# TK510_Signalbakplan_-_Kopi.net
KiCad netlist of a schematic drawn in Altium Designer
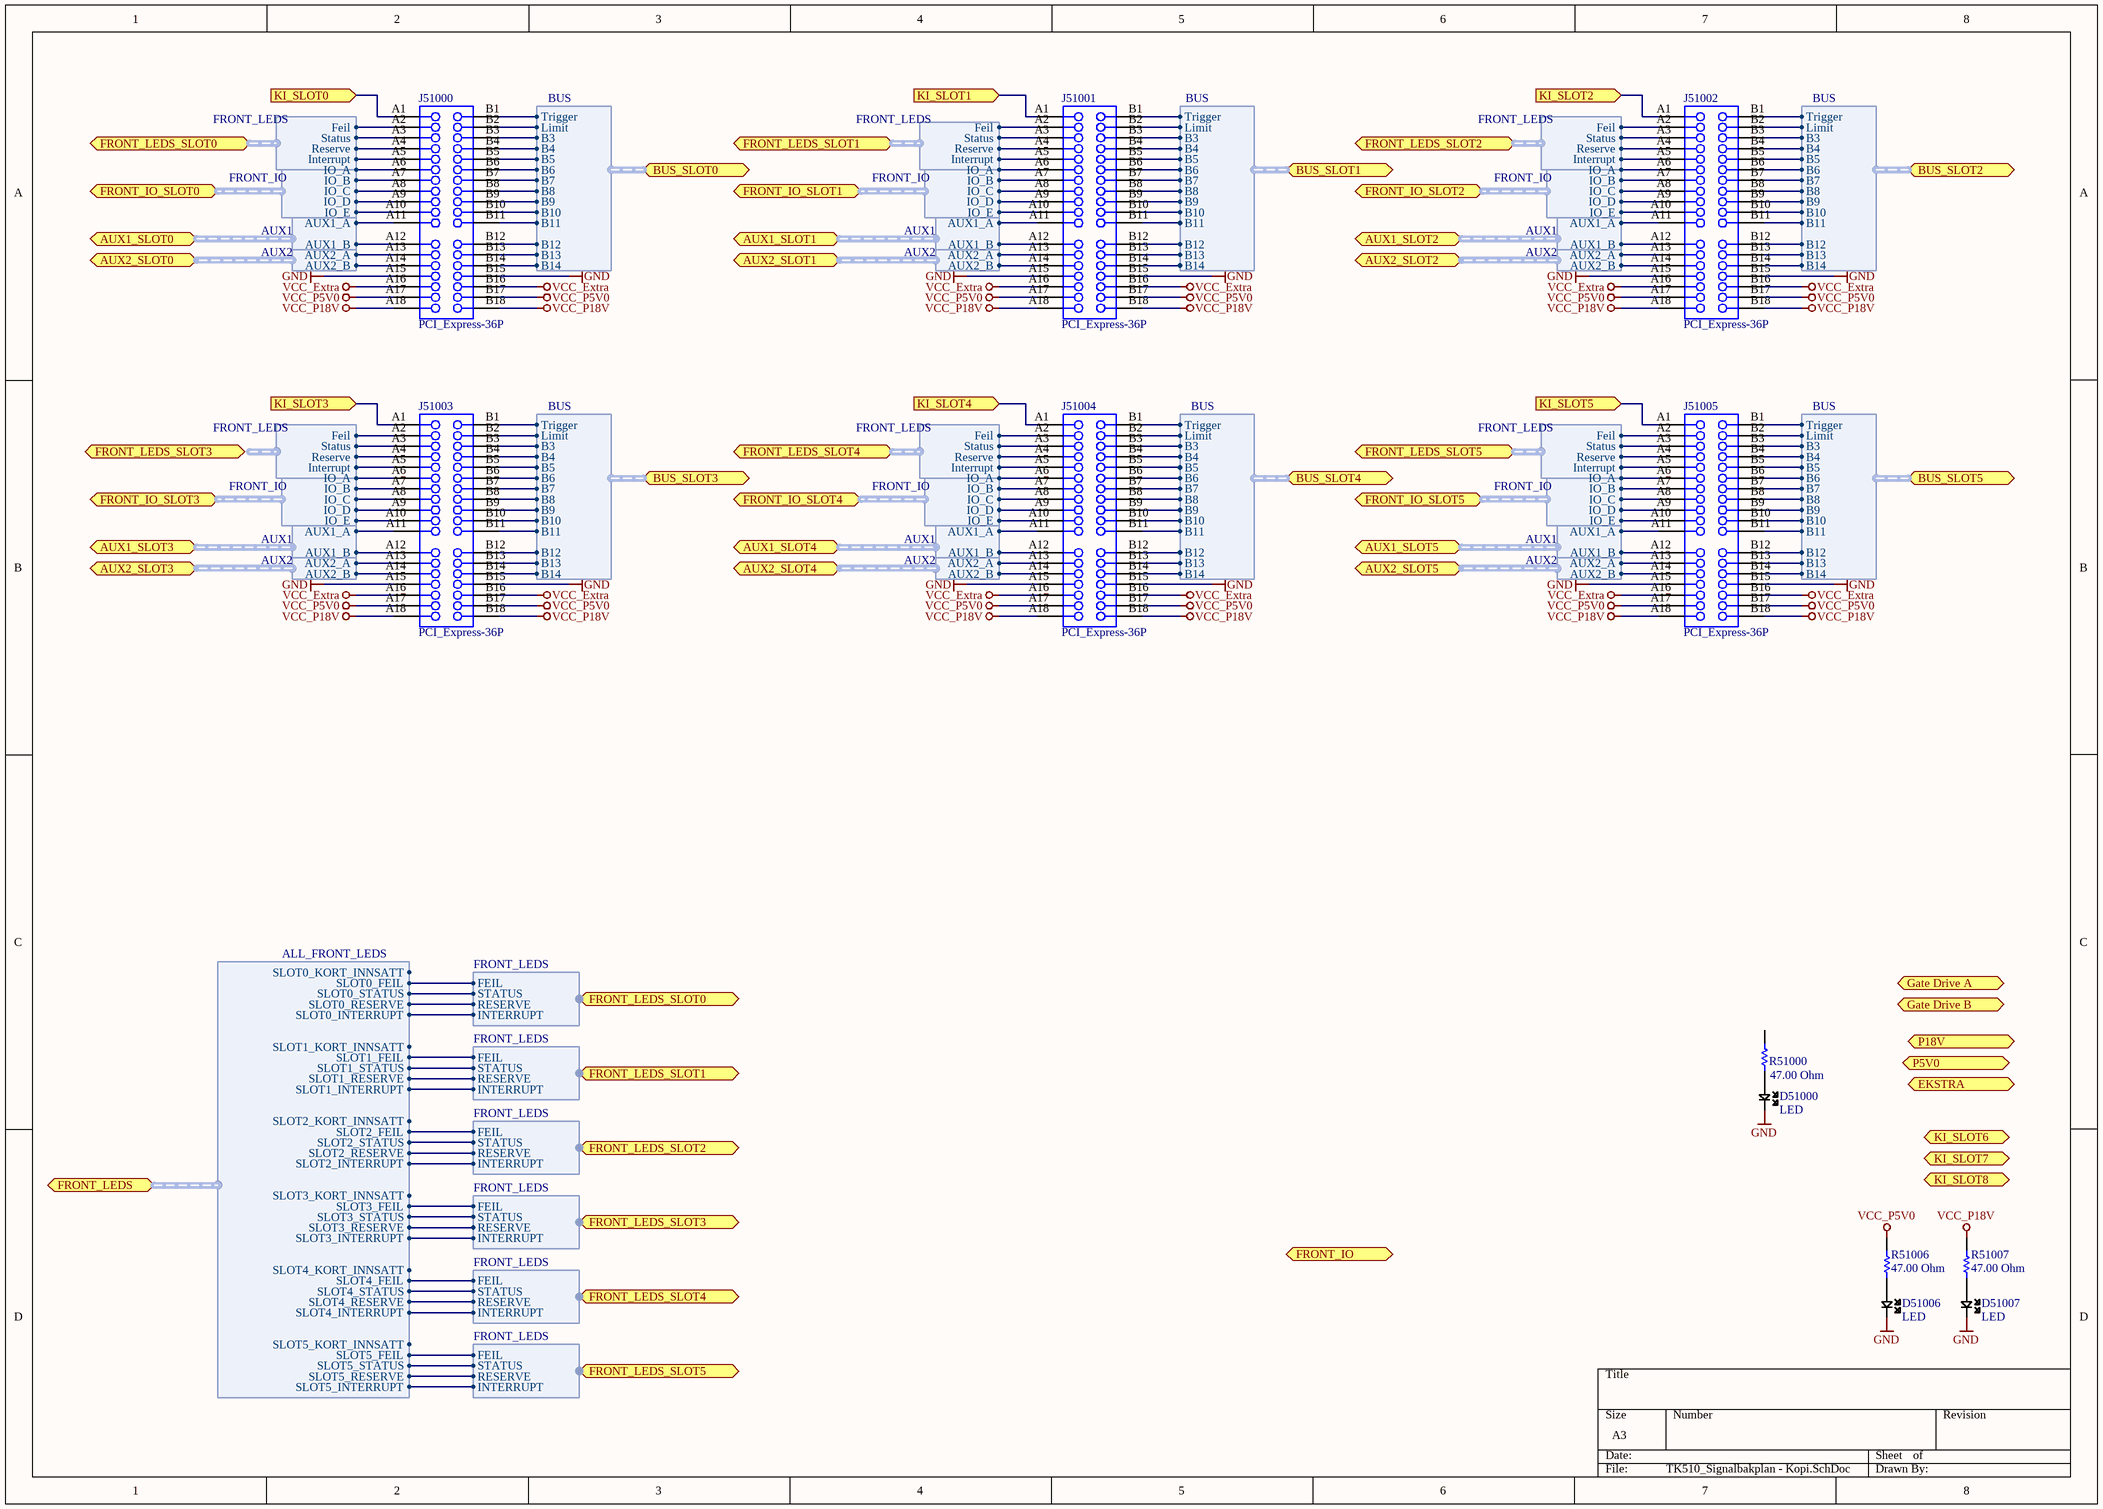
[diagram p0: TK510_Signalbakplan - Kopi.SchDoc]

(export (version "E")
  (design (tool "Eeschema 10.0.6"))
  (components
    (comp (ref "D51000")
      (value "LED")
      (footprint "I_LEDC0603(1608)_N")
      (libsource (lib "OVLib") (part "LED"))
    )
    (comp (ref "D51006")
      (value "LED")
      (footprint "I_LEDC0603(1608)_N")
      (libsource (lib "OVLib") (part "LED"))
    )
    (comp (ref "D51007")
      (value "LED")
      (footprint "I_LEDC0603(1608)_N")
      (libsource (lib "OVLib") (part "LED"))
    )
    (comp (ref "J51000")
      (value "PCI_Express-36P")
      (footprint "PCI_Express-36P")
      (description "Board-to-Board Connector, PTH, Vertical, Pitch 1.00mm, 36-Position")
      (libsource (lib "OVLib") (part "PCI_Express-36P"))
    )
    (comp (ref "J51001")
      (value "PCI_Express-36P")
      (footprint "PCI_Express-36P")
      (description "Board-to-Board Connector, PTH, Vertical, Pitch 1.00mm, 36-Position")
      (libsource (lib "OVLib") (part "PCI_Express-36P"))
    )
    (comp (ref "J51002")
      (value "PCI_Express-36P")
      (footprint "PCI_Express-36P")
      (description "Board-to-Board Connector, PTH, Vertical, Pitch 1.00mm, 36-Position")
      (libsource (lib "OVLib") (part "PCI_Express-36P"))
    )
    (comp (ref "J51003")
      (value "PCI_Express-36P")
      (footprint "PCI_Express-36P")
      (description "Board-to-Board Connector, PTH, Vertical, Pitch 1.00mm, 36-Position")
      (libsource (lib "OVLib") (part "PCI_Express-36P"))
    )
    (comp (ref "J51004")
      (value "PCI_Express-36P")
      (footprint "PCI_Express-36P")
      (description "Board-to-Board Connector, PTH, Vertical, Pitch 1.00mm, 36-Position")
      (libsource (lib "OVLib") (part "PCI_Express-36P"))
    )
    (comp (ref "J51005")
      (value "PCI_Express-36P")
      (footprint "PCI_Express-36P")
      (description "Board-to-Board Connector, PTH, Vertical, Pitch 1.00mm, 36-Position")
      (libsource (lib "OVLib") (part "PCI_Express-36P"))
    )
    (comp (ref "R51000")
      (value "47.00 Ohm")
      (footprint "RESC0603(1608)_M")
      (description "47R 0.1W 5% 0603 (1608 Metric)  SMD")
      (fields (field (name "TOLERANCE") "5 %") (field (name "POWER") "0.1 W"))
      (libsource (lib "Altium Content Vault") (part "CMP-1012-00042-1"))
    )
    (comp (ref "R51006")
      (value "47.00 Ohm")
      (footprint "RESC0603(1608)_M")
      (description "47R 0.1W 5% 0603 (1608 Metric)  SMD")
      (fields (field (name "TOLERANCE") "5 %") (field (name "POWER") "0.1 W"))
      (libsource (lib "Altium Content Vault") (part "CMP-1012-00042-1"))
    )
    (comp (ref "R51007")
      (value "47.00 Ohm")
      (footprint "RESC0603(1608)_M")
      (description "47R 0.1W 5% 0603 (1608 Metric)  SMD")
      (fields (field (name "TOLERANCE") "5 %") (field (name "POWER") "0.1 W"))
      (libsource (lib "Altium Content Vault") (part "CMP-1012-00042-1"))
    )
  )
  (nets
    (net (code "20") (name "/KI_SLOT0") (class "Default")
      (node (ref "J51000") (pin "A1") (pinfunction "A1_A1") (pintype "passive"))
    )
    (net (code "21") (name "/KI_SLOT1") (class "Default")
      (node (ref "J51001") (pin "A1") (pinfunction "A1_A1") (pintype "passive"))
    )
    (net (code "22") (name "/KI_SLOT2") (class "Default")
      (node (ref "J51002") (pin "A1") (pinfunction "A1_A1") (pintype "passive"))
    )
    (net (code "23") (name "/KI_SLOT3") (class "Default")
      (node (ref "J51003") (pin "A1") (pinfunction "A1_A1") (pintype "passive"))
    )
    (net (code "24") (name "/KI_SLOT4") (class "Default")
      (node (ref "J51004") (pin "A1") (pinfunction "A1_A1") (pintype "passive"))
    )
    (net (code "25") (name "/KI_SLOT5") (class "Default")
      (node (ref "J51005") (pin "A1") (pinfunction "A1_A1") (pintype "passive"))
    )
    (net (code "35") (name "GND") (class "Default")
      (node (ref "D51000") (pin "2") (pinfunction "2_2") (pintype "passive"))
      (node (ref "D51006") (pin "2") (pinfunction "2_2") (pintype "passive"))
      (node (ref "D51007") (pin "2") (pinfunction "2_2") (pintype "passive"))
      (node (ref "J51000") (pin "A15") (pinfunction "A15_A15") (pintype "passive"))
      (node (ref "J51000") (pin "B15") (pinfunction "B15_B15") (pintype "passive"))
      (node (ref "J51001") (pin "A15") (pinfunction "A15_A15") (pintype "passive"))
      (node (ref "J51001") (pin "B15") (pinfunction "B15_B15") (pintype "passive"))
      (node (ref "J51002") (pin "A15") (pinfunction "A15_A15") (pintype "passive"))
      (node (ref "J51002") (pin "B15") (pinfunction "B15_B15") (pintype "passive"))
      (node (ref "J51003") (pin "A15") (pinfunction "A15_A15") (pintype "passive"))
      (node (ref "J51003") (pin "B15") (pinfunction "B15_B15") (pintype "passive"))
      (node (ref "J51004") (pin "A15") (pinfunction "A15_A15") (pintype "passive"))
      (node (ref "J51004") (pin "B15") (pinfunction "B15_B15") (pintype "passive"))
      (node (ref "J51005") (pin "A15") (pinfunction "A15_A15") (pintype "passive"))
      (node (ref "J51005") (pin "B15") (pinfunction "B15_B15") (pintype "passive"))
    )
    (net (code "36") (name "Net-(D51000-Pad1)") (class "Default")
      (node (ref "D51000") (pin "1") (pinfunction "1_1") (pintype "passive"))
      (node (ref "R51000") (pin "1") (pinfunction "1_1") (pintype "passive"))
    )
    (net (code "37") (name "Net-(D51006-Pad1)") (class "Default")
      (node (ref "D51006") (pin "1") (pinfunction "1_1") (pintype "passive"))
      (node (ref "R51006") (pin "2") (pinfunction "2_2") (pintype "passive"))
    )
    (net (code "38") (name "Net-(D51007-Pad1)") (class "Default")
      (node (ref "D51007") (pin "1") (pinfunction "1_1") (pintype "passive"))
      (node (ref "R51007") (pin "2") (pinfunction "2_2") (pintype "passive"))
    )
    (net (code "39") (name "VCC_Extra") (class "Default")
      (node (ref "J51000") (pin "A16") (pinfunction "A16_A16") (pintype "passive"))
      (node (ref "J51000") (pin "B16") (pinfunction "B16_B16") (pintype "passive"))
      (node (ref "J51001") (pin "A16") (pinfunction "A16_A16") (pintype "passive"))
      (node (ref "J51001") (pin "B16") (pinfunction "B16_B16") (pintype "passive"))
      (node (ref "J51002") (pin "A16") (pinfunction "A16_A16") (pintype "passive"))
      (node (ref "J51002") (pin "B16") (pinfunction "B16_B16") (pintype "passive"))
      (node (ref "J51003") (pin "A16") (pinfunction "A16_A16") (pintype "passive"))
      (node (ref "J51003") (pin "B16") (pinfunction "B16_B16") (pintype "passive"))
      (node (ref "J51004") (pin "A16") (pinfunction "A16_A16") (pintype "passive"))
      (node (ref "J51004") (pin "B16") (pinfunction "B16_B16") (pintype "passive"))
      (node (ref "J51005") (pin "A16") (pinfunction "A16_A16") (pintype "passive"))
      (node (ref "J51005") (pin "B16") (pinfunction "B16_B16") (pintype "passive"))
    )
    (net (code "40") (name "VCC_P5V0") (class "Default")
      (node (ref "J51000") (pin "A17") (pinfunction "A17_A17") (pintype "passive"))
      (node (ref "J51000") (pin "B17") (pinfunction "B17_B17") (pintype "passive"))
      (node (ref "J51001") (pin "A17") (pinfunction "A17_A17") (pintype "passive"))
      (node (ref "J51001") (pin "B17") (pinfunction "B17_B17") (pintype "passive"))
      (node (ref "J51002") (pin "A17") (pinfunction "A17_A17") (pintype "passive"))
      (node (ref "J51002") (pin "B17") (pinfunction "B17_B17") (pintype "passive"))
      (node (ref "J51003") (pin "A17") (pinfunction "A17_A17") (pintype "passive"))
      (node (ref "J51003") (pin "B17") (pinfunction "B17_B17") (pintype "passive"))
      (node (ref "J51004") (pin "A17") (pinfunction "A17_A17") (pintype "passive"))
      (node (ref "J51004") (pin "B17") (pinfunction "B17_B17") (pintype "passive"))
      (node (ref "J51005") (pin "A17") (pinfunction "A17_A17") (pintype "passive"))
      (node (ref "J51005") (pin "B17") (pinfunction "B17_B17") (pintype "passive"))
      (node (ref "R51006") (pin "1") (pinfunction "1_1") (pintype "passive"))
    )
    (net (code "41") (name "VCC_P18V") (class "Default")
      (node (ref "J51000") (pin "A18") (pinfunction "A18_A18") (pintype "passive"))
      (node (ref "J51000") (pin "B18") (pinfunction "B18_B18") (pintype "passive"))
      (node (ref "J51001") (pin "A18") (pinfunction "A18_A18") (pintype "passive"))
      (node (ref "J51001") (pin "B18") (pinfunction "B18_B18") (pintype "passive"))
      (node (ref "J51002") (pin "A18") (pinfunction "A18_A18") (pintype "passive"))
      (node (ref "J51002") (pin "B18") (pinfunction "B18_B18") (pintype "passive"))
      (node (ref "J51003") (pin "A18") (pinfunction "A18_A18") (pintype "passive"))
      (node (ref "J51003") (pin "B18") (pinfunction "B18_B18") (pintype "passive"))
      (node (ref "J51004") (pin "A18") (pinfunction "A18_A18") (pintype "passive"))
      (node (ref "J51004") (pin "B18") (pinfunction "B18_B18") (pintype "passive"))
      (node (ref "J51005") (pin "A18") (pinfunction "A18_A18") (pintype "passive"))
      (node (ref "J51005") (pin "B18") (pinfunction "B18_B18") (pintype "passive"))
      (node (ref "R51007") (pin "1") (pinfunction "1_1") (pintype "passive"))
    )
    (net (code "42") (name "unconnected-(J51000-PadA2)") (class "Default")
      (node (ref "J51000") (pin "A2") (pinfunction "A2_A2") (pintype "passive"))
    )
    (net (code "43") (name "unconnected-(J51000-PadA3)") (class "Default")
      (node (ref "J51000") (pin "A3") (pinfunction "A3_A3") (pintype "passive"))
    )
    (net (code "44") (name "unconnected-(J51000-PadA4)") (class "Default")
      (node (ref "J51000") (pin "A4") (pinfunction "A4_A4") (pintype "passive"))
    )
    (net (code "45") (name "unconnected-(J51000-PadA5)") (class "Default")
      (node (ref "J51000") (pin "A5") (pinfunction "A5_A5") (pintype "passive"))
    )
    (net (code "46") (name "unconnected-(J51000-PadA6)") (class "Default")
      (node (ref "J51000") (pin "A6") (pinfunction "A6_A6") (pintype "passive"))
    )
    (net (code "47") (name "unconnected-(J51000-PadA7)") (class "Default")
      (node (ref "J51000") (pin "A7") (pinfunction "A7_A7") (pintype "passive"))
    )
    (net (code "48") (name "unconnected-(J51000-PadA8)") (class "Default")
      (node (ref "J51000") (pin "A8") (pinfunction "A8_A8") (pintype "passive"))
    )
    (net (code "49") (name "unconnected-(J51000-PadA9)") (class "Default")
      (node (ref "J51000") (pin "A9") (pinfunction "A9_A9") (pintype "passive"))
    )
    (net (code "50") (name "unconnected-(J51000-PadA10)") (class "Default")
      (node (ref "J51000") (pin "A10") (pinfunction "A10_A10") (pintype "passive"))
    )
    (net (code "51") (name "unconnected-(J51000-PadA11)") (class "Default")
      (node (ref "J51000") (pin "A11") (pinfunction "A11_A11") (pintype "passive"))
    )
    (net (code "52") (name "unconnected-(J51000-PadA12)") (class "Default")
      (node (ref "J51000") (pin "A12") (pinfunction "A12_A12") (pintype "passive"))
    )
    (net (code "53") (name "unconnected-(J51000-PadA13)") (class "Default")
      (node (ref "J51000") (pin "A13") (pinfunction "A13_A13") (pintype "passive"))
    )
    (net (code "54") (name "unconnected-(J51000-PadA14)") (class "Default")
      (node (ref "J51000") (pin "A14") (pinfunction "A14_A14") (pintype "passive"))
    )
    (net (code "55") (name "unconnected-(J51000-PadB1)") (class "Default")
      (node (ref "J51000") (pin "B1") (pinfunction "B1_B1") (pintype "passive"))
    )
    (net (code "56") (name "unconnected-(J51000-PadB2)") (class "Default")
      (node (ref "J51000") (pin "B2") (pinfunction "B2_B2") (pintype "passive"))
    )
    (net (code "57") (name "unconnected-(J51000-PadB3)") (class "Default")
      (node (ref "J51000") (pin "B3") (pinfunction "B3_B3") (pintype "passive"))
    )
    (net (code "58") (name "unconnected-(J51000-PadB4)") (class "Default")
      (node (ref "J51000") (pin "B4") (pinfunction "B4_B4") (pintype "passive"))
    )
    (net (code "59") (name "unconnected-(J51000-PadB5)") (class "Default")
      (node (ref "J51000") (pin "B5") (pinfunction "B5_B5") (pintype "passive"))
    )
    (net (code "60") (name "unconnected-(J51000-PadB6)") (class "Default")
      (node (ref "J51000") (pin "B6") (pinfunction "B6_B6") (pintype "passive"))
    )
    (net (code "61") (name "unconnected-(J51000-PadB7)") (class "Default")
      (node (ref "J51000") (pin "B7") (pinfunction "B7_B7") (pintype "passive"))
    )
    (net (code "62") (name "unconnected-(J51000-PadB8)") (class "Default")
      (node (ref "J51000") (pin "B8") (pinfunction "B8_B8") (pintype "passive"))
    )
    (net (code "63") (name "unconnected-(J51000-PadB9)") (class "Default")
      (node (ref "J51000") (pin "B9") (pinfunction "B9_B9") (pintype "passive"))
    )
    (net (code "64") (name "unconnected-(J51000-PadB10)") (class "Default")
      (node (ref "J51000") (pin "B10") (pinfunction "B10_B10") (pintype "passive"))
    )
    (net (code "65") (name "unconnected-(J51000-PadB11)") (class "Default")
      (node (ref "J51000") (pin "B11") (pinfunction "B11_B11") (pintype "passive"))
    )
    (net (code "66") (name "unconnected-(J51000-PadB12)") (class "Default")
      (node (ref "J51000") (pin "B12") (pinfunction "B12_B12") (pintype "passive"))
    )
    (net (code "67") (name "unconnected-(J51000-PadB13)") (class "Default")
      (node (ref "J51000") (pin "B13") (pinfunction "B13_B13") (pintype "passive"))
    )
    (net (code "68") (name "unconnected-(J51000-PadB14)") (class "Default")
      (node (ref "J51000") (pin "B14") (pinfunction "B14_B14") (pintype "passive"))
    )
    (net (code "69") (name "unconnected-(J51001-PadA2)") (class "Default")
      (node (ref "J51001") (pin "A2") (pinfunction "A2_A2") (pintype "passive"))
    )
    (net (code "70") (name "unconnected-(J51001-PadA3)") (class "Default")
      (node (ref "J51001") (pin "A3") (pinfunction "A3_A3") (pintype "passive"))
    )
    (net (code "71") (name "unconnected-(J51001-PadA4)") (class "Default")
      (node (ref "J51001") (pin "A4") (pinfunction "A4_A4") (pintype "passive"))
    )
    (net (code "72") (name "unconnected-(J51001-PadA5)") (class "Default")
      (node (ref "J51001") (pin "A5") (pinfunction "A5_A5") (pintype "passive"))
    )
    (net (code "73") (name "unconnected-(J51001-PadA6)") (class "Default")
      (node (ref "J51001") (pin "A6") (pinfunction "A6_A6") (pintype "passive"))
    )
    (net (code "74") (name "unconnected-(J51001-PadA7)") (class "Default")
      (node (ref "J51001") (pin "A7") (pinfunction "A7_A7") (pintype "passive"))
    )
    (net (code "75") (name "unconnected-(J51001-PadA8)") (class "Default")
      (node (ref "J51001") (pin "A8") (pinfunction "A8_A8") (pintype "passive"))
    )
    (net (code "76") (name "unconnected-(J51001-PadA9)") (class "Default")
      (node (ref "J51001") (pin "A9") (pinfunction "A9_A9") (pintype "passive"))
    )
    (net (code "77") (name "unconnected-(J51001-PadA10)") (class "Default")
      (node (ref "J51001") (pin "A10") (pinfunction "A10_A10") (pintype "passive"))
    )
    (net (code "78") (name "unconnected-(J51001-PadA11)") (class "Default")
      (node (ref "J51001") (pin "A11") (pinfunction "A11_A11") (pintype "passive"))
    )
    (net (code "79") (name "unconnected-(J51001-PadA12)") (class "Default")
      (node (ref "J51001") (pin "A12") (pinfunction "A12_A12") (pintype "passive"))
    )
    (net (code "80") (name "unconnected-(J51001-PadA13)") (class "Default")
      (node (ref "J51001") (pin "A13") (pinfunction "A13_A13") (pintype "passive"))
    )
    (net (code "81") (name "unconnected-(J51001-PadA14)") (class "Default")
      (node (ref "J51001") (pin "A14") (pinfunction "A14_A14") (pintype "passive"))
    )
    (net (code "82") (name "unconnected-(J51001-PadB1)") (class "Default")
      (node (ref "J51001") (pin "B1") (pinfunction "B1_B1") (pintype "passive"))
    )
    (net (code "83") (name "unconnected-(J51001-PadB2)") (class "Default")
      (node (ref "J51001") (pin "B2") (pinfunction "B2_B2") (pintype "passive"))
    )
    (net (code "84") (name "unconnected-(J51001-PadB3)") (class "Default")
      (node (ref "J51001") (pin "B3") (pinfunction "B3_B3") (pintype "passive"))
    )
    (net (code "85") (name "unconnected-(J51001-PadB4)") (class "Default")
      (node (ref "J51001") (pin "B4") (pinfunction "B4_B4") (pintype "passive"))
    )
    (net (code "86") (name "unconnected-(J51001-PadB5)") (class "Default")
      (node (ref "J51001") (pin "B5") (pinfunction "B5_B5") (pintype "passive"))
    )
    (net (code "87") (name "unconnected-(J51001-PadB6)") (class "Default")
      (node (ref "J51001") (pin "B6") (pinfunction "B6_B6") (pintype "passive"))
    )
    (net (code "88") (name "unconnected-(J51001-PadB7)") (class "Default")
      (node (ref "J51001") (pin "B7") (pinfunction "B7_B7") (pintype "passive"))
    )
    (net (code "89") (name "unconnected-(J51001-PadB8)") (class "Default")
      (node (ref "J51001") (pin "B8") (pinfunction "B8_B8") (pintype "passive"))
    )
    (net (code "90") (name "unconnected-(J51001-PadB9)") (class "Default")
      (node (ref "J51001") (pin "B9") (pinfunction "B9_B9") (pintype "passive"))
    )
    (net (code "91") (name "unconnected-(J51001-PadB10)") (class "Default")
      (node (ref "J51001") (pin "B10") (pinfunction "B10_B10") (pintype "passive"))
    )
    (net (code "92") (name "unconnected-(J51001-PadB11)") (class "Default")
      (node (ref "J51001") (pin "B11") (pinfunction "B11_B11") (pintype "passive"))
    )
    (net (code "93") (name "unconnected-(J51001-PadB12)") (class "Default")
      (node (ref "J51001") (pin "B12") (pinfunction "B12_B12") (pintype "passive"))
    )
    (net (code "94") (name "unconnected-(J51001-PadB13)") (class "Default")
      (node (ref "J51001") (pin "B13") (pinfunction "B13_B13") (pintype "passive"))
    )
    (net (code "95") (name "unconnected-(J51001-PadB14)") (class "Default")
      (node (ref "J51001") (pin "B14") (pinfunction "B14_B14") (pintype "passive"))
    )
    (net (code "96") (name "unconnected-(J51002-PadA2)") (class "Default")
      (node (ref "J51002") (pin "A2") (pinfunction "A2_A2") (pintype "passive"))
    )
    (net (code "97") (name "unconnected-(J51002-PadA3)") (class "Default")
      (node (ref "J51002") (pin "A3") (pinfunction "A3_A3") (pintype "passive"))
    )
    (net (code "98") (name "unconnected-(J51002-PadA4)") (class "Default")
      (node (ref "J51002") (pin "A4") (pinfunction "A4_A4") (pintype "passive"))
    )
    (net (code "99") (name "unconnected-(J51002-PadA5)") (class "Default")
      (node (ref "J51002") (pin "A5") (pinfunction "A5_A5") (pintype "passive"))
    )
    (net (code "100") (name "unconnected-(J51002-PadA6)") (class "Default")
      (node (ref "J51002") (pin "A6") (pinfunction "A6_A6") (pintype "passive"))
    )
    (net (code "101") (name "unconnected-(J51002-PadA7)") (class "Default")
      (node (ref "J51002") (pin "A7") (pinfunction "A7_A7") (pintype "passive"))
    )
    (net (code "102") (name "unconnected-(J51002-PadA8)") (class "Default")
      (node (ref "J51002") (pin "A8") (pinfunction "A8_A8") (pintype "passive"))
    )
    (net (code "103") (name "unconnected-(J51002-PadA9)") (class "Default")
      (node (ref "J51002") (pin "A9") (pinfunction "A9_A9") (pintype "passive"))
    )
    (net (code "104") (name "unconnected-(J51002-PadA10)") (class "Default")
      (node (ref "J51002") (pin "A10") (pinfunction "A10_A10") (pintype "passive"))
    )
    (net (code "105") (name "unconnected-(J51002-PadA11)") (class "Default")
      (node (ref "J51002") (pin "A11") (pinfunction "A11_A11") (pintype "passive"))
    )
    (net (code "106") (name "unconnected-(J51002-PadA12)") (class "Default")
      (node (ref "J51002") (pin "A12") (pinfunction "A12_A12") (pintype "passive"))
    )
    (net (code "107") (name "unconnected-(J51002-PadA13)") (class "Default")
      (node (ref "J51002") (pin "A13") (pinfunction "A13_A13") (pintype "passive"))
    )
    (net (code "108") (name "unconnected-(J51002-PadA14)") (class "Default")
      (node (ref "J51002") (pin "A14") (pinfunction "A14_A14") (pintype "passive"))
    )
    (net (code "109") (name "unconnected-(J51002-PadB1)") (class "Default")
      (node (ref "J51002") (pin "B1") (pinfunction "B1_B1") (pintype "passive"))
    )
    (net (code "110") (name "unconnected-(J51002-PadB2)") (class "Default")
      (node (ref "J51002") (pin "B2") (pinfunction "B2_B2") (pintype "passive"))
    )
    (net (code "111") (name "unconnected-(J51002-PadB3)") (class "Default")
      (node (ref "J51002") (pin "B3") (pinfunction "B3_B3") (pintype "passive"))
    )
    (net (code "112") (name "unconnected-(J51002-PadB4)") (class "Default")
      (node (ref "J51002") (pin "B4") (pinfunction "B4_B4") (pintype "passive"))
    )
    (net (code "113") (name "unconnected-(J51002-PadB5)") (class "Default")
      (node (ref "J51002") (pin "B5") (pinfunction "B5_B5") (pintype "passive"))
    )
    (net (code "114") (name "unconnected-(J51002-PadB6)") (class "Default")
      (node (ref "J51002") (pin "B6") (pinfunction "B6_B6") (pintype "passive"))
    )
    (net (code "115") (name "unconnected-(J51002-PadB7)") (class "Default")
      (node (ref "J51002") (pin "B7") (pinfunction "B7_B7") (pintype "passive"))
    )
    (net (code "116") (name "unconnected-(J51002-PadB8)") (class "Default")
      (node (ref "J51002") (pin "B8") (pinfunction "B8_B8") (pintype "passive"))
    )
    (net (code "117") (name "unconnected-(J51002-PadB9)") (class "Default")
      (node (ref "J51002") (pin "B9") (pinfunction "B9_B9") (pintype "passive"))
    )
    (net (code "118") (name "unconnected-(J51002-PadB10)") (class "Default")
      (node (ref "J51002") (pin "B10") (pinfunction "B10_B10") (pintype "passive"))
    )
    (net (code "119") (name "unconnected-(J51002-PadB11)") (class "Default")
      (node (ref "J51002") (pin "B11") (pinfunction "B11_B11") (pintype "passive"))
    )
    (net (code "120") (name "unconnected-(J51002-PadB12)") (class "Default")
      (node (ref "J51002") (pin "B12") (pinfunction "B12_B12") (pintype "passive"))
    )
    (net (code "121") (name "unconnected-(J51002-PadB13)") (class "Default")
      (node (ref "J51002") (pin "B13") (pinfunction "B13_B13") (pintype "passive"))
    )
    (net (code "122") (name "unconnected-(J51002-PadB14)") (class "Default")
      (node (ref "J51002") (pin "B14") (pinfunction "B14_B14") (pintype "passive"))
    )
    (net (code "123") (name "unconnected-(J51003-PadA2)") (class "Default")
      (node (ref "J51003") (pin "A2") (pinfunction "A2_A2") (pintype "passive"))
    )
    (net (code "124") (name "unconnected-(J51003-PadA3)") (class "Default")
      (node (ref "J51003") (pin "A3") (pinfunction "A3_A3") (pintype "passive"))
    )
    (net (code "125") (name "unconnected-(J51003-PadA4)") (class "Default")
      (node (ref "J51003") (pin "A4") (pinfunction "A4_A4") (pintype "passive"))
    )
    (net (code "126") (name "unconnected-(J51003-PadA5)") (class "Default")
      (node (ref "J51003") (pin "A5") (pinfunction "A5_A5") (pintype "passive"))
    )
    (net (code "127") (name "unconnected-(J51003-PadA6)") (class "Default")
      (node (ref "J51003") (pin "A6") (pinfunction "A6_A6") (pintype "passive"))
    )
    (net (code "128") (name "unconnected-(J51003-PadA7)") (class "Default")
      (node (ref "J51003") (pin "A7") (pinfunction "A7_A7") (pintype "passive"))
    )
    (net (code "129") (name "unconnected-(J51003-PadA8)") (class "Default")
      (node (ref "J51003") (pin "A8") (pinfunction "A8_A8") (pintype "passive"))
    )
    (net (code "130") (name "unconnected-(J51003-PadA9)") (class "Default")
      (node (ref "J51003") (pin "A9") (pinfunction "A9_A9") (pintype "passive"))
    )
    (net (code "131") (name "unconnected-(J51003-PadA10)") (class "Default")
      (node (ref "J51003") (pin "A10") (pinfunction "A10_A10") (pintype "passive"))
    )
    (net (code "132") (name "unconnected-(J51003-PadA11)") (class "Default")
      (node (ref "J51003") (pin "A11") (pinfunction "A11_A11") (pintype "passive"))
    )
    (net (code "133") (name "unconnected-(J51003-PadA12)") (class "Default")
      (node (ref "J51003") (pin "A12") (pinfunction "A12_A12") (pintype "passive"))
    )
    (net (code "134") (name "unconnected-(J51003-PadA13)") (class "Default")
      (node (ref "J51003") (pin "A13") (pinfunction "A13_A13") (pintype "passive"))
    )
    (net (code "135") (name "unconnected-(J51003-PadA14)") (class "Default")
      (node (ref "J51003") (pin "A14") (pinfunction "A14_A14") (pintype "passive"))
    )
    (net (code "136") (name "unconnected-(J51003-PadB1)") (class "Default")
      (node (ref "J51003") (pin "B1") (pinfunction "B1_B1") (pintype "passive"))
    )
    (net (code "137") (name "unconnected-(J51003-PadB2)") (class "Default")
      (node (ref "J51003") (pin "B2") (pinfunction "B2_B2") (pintype "passive"))
    )
    (net (code "138") (name "unconnected-(J51003-PadB3)") (class "Default")
      (node (ref "J51003") (pin "B3") (pinfunction "B3_B3") (pintype "passive"))
    )
    (net (code "139") (name "unconnected-(J51003-PadB4)") (class "Default")
      (node (ref "J51003") (pin "B4") (pinfunction "B4_B4") (pintype "passive"))
    )
    (net (code "140") (name "unconnected-(J51003-PadB5)") (class "Default")
      (node (ref "J51003") (pin "B5") (pinfunction "B5_B5") (pintype "passive"))
    )
    (net (code "141") (name "unconnected-(J51003-PadB6)") (class "Default")
      (node (ref "J51003") (pin "B6") (pinfunction "B6_B6") (pintype "passive"))
    )
    (net (code "142") (name "unconnected-(J51003-PadB7)") (class "Default")
      (node (ref "J51003") (pin "B7") (pinfunction "B7_B7") (pintype "passive"))
    )
    (net (code "143") (name "unconnected-(J51003-PadB8)") (class "Default")
      (node (ref "J51003") (pin "B8") (pinfunction "B8_B8") (pintype "passive"))
    )
    (net (code "144") (name "unconnected-(J51003-PadB9)") (class "Default")
      (node (ref "J51003") (pin "B9") (pinfunction "B9_B9") (pintype "passive"))
    )
    (net (code "145") (name "unconnected-(J51003-PadB10)") (class "Default")
      (node (ref "J51003") (pin "B10") (pinfunction "B10_B10") (pintype "passive"))
    )
    (net (code "146") (name "unconnected-(J51003-PadB11)") (class "Default")
      (node (ref "J51003") (pin "B11") (pinfunction "B11_B11") (pintype "passive"))
    )
    (net (code "147") (name "unconnected-(J51003-PadB12)") (class "Default")
      (node (ref "J51003") (pin "B12") (pinfunction "B12_B12") (pintype "passive"))
    )
    (net (code "148") (name "unconnected-(J51003-PadB13)") (class "Default")
      (node (ref "J51003") (pin "B13") (pinfunction "B13_B13") (pintype "passive"))
    )
    (net (code "149") (name "unconnected-(J51003-PadB14)") (class "Default")
      (node (ref "J51003") (pin "B14") (pinfunction "B14_B14") (pintype "passive"))
    )
    (net (code "150") (name "unconnected-(J51004-PadA2)") (class "Default")
      (node (ref "J51004") (pin "A2") (pinfunction "A2_A2") (pintype "passive"))
    )
    (net (code "151") (name "unconnected-(J51004-PadA3)") (class "Default")
      (node (ref "J51004") (pin "A3") (pinfunction "A3_A3") (pintype "passive"))
    )
    (net (code "152") (name "unconnected-(J51004-PadA4)") (class "Default")
      (node (ref "J51004") (pin "A4") (pinfunction "A4_A4") (pintype "passive"))
    )
    (net (code "153") (name "unconnected-(J51004-PadA5)") (class "Default")
      (node (ref "J51004") (pin "A5") (pinfunction "A5_A5") (pintype "passive"))
    )
    (net (code "154") (name "unconnected-(J51004-PadA6)") (class "Default")
      (node (ref "J51004") (pin "A6") (pinfunction "A6_A6") (pintype "passive"))
    )
    (net (code "155") (name "unconnected-(J51004-PadA7)") (class "Default")
      (node (ref "J51004") (pin "A7") (pinfunction "A7_A7") (pintype "passive"))
    )
    (net (code "156") (name "unconnected-(J51004-PadA8)") (class "Default")
      (node (ref "J51004") (pin "A8") (pinfunction "A8_A8") (pintype "passive"))
    )
    (net (code "157") (name "unconnected-(J51004-PadA9)") (class "Default")
      (node (ref "J51004") (pin "A9") (pinfunction "A9_A9") (pintype "passive"))
    )
    (net (code "158") (name "unconnected-(J51004-PadA10)") (class "Default")
      (node (ref "J51004") (pin "A10") (pinfunction "A10_A10") (pintype "passive"))
    )
    (net (code "159") (name "unconnected-(J51004-PadA11)") (class "Default")
      (node (ref "J51004") (pin "A11") (pinfunction "A11_A11") (pintype "passive"))
    )
    (net (code "160") (name "unconnected-(J51004-PadA12)") (class "Default")
      (node (ref "J51004") (pin "A12") (pinfunction "A12_A12") (pintype "passive"))
    )
    (net (code "161") (name "unconnected-(J51004-PadA13)") (class "Default")
      (node (ref "J51004") (pin "A13") (pinfunction "A13_A13") (pintype "passive"))
    )
    (net (code "162") (name "unconnected-(J51004-PadA14)") (class "Default")
      (node (ref "J51004") (pin "A14") (pinfunction "A14_A14") (pintype "passive"))
    )
    (net (code "163") (name "unconnected-(J51004-PadB1)") (class "Default")
      (node (ref "J51004") (pin "B1") (pinfunction "B1_B1") (pintype "passive"))
    )
    (net (code "164") (name "unconnected-(J51004-PadB2)") (class "Default")
      (node (ref "J51004") (pin "B2") (pinfunction "B2_B2") (pintype "passive"))
    )
    (net (code "165") (name "unconnected-(J51004-PadB3)") (class "Default")
      (node (ref "J51004") (pin "B3") (pinfunction "B3_B3") (pintype "passive"))
    )
    (net (code "166") (name "unconnected-(J51004-PadB4)") (class "Default")
      (node (ref "J51004") (pin "B4") (pinfunction "B4_B4") (pintype "passive"))
    )
    (net (code "167") (name "unconnected-(J51004-PadB5)") (class "Default")
      (node (ref "J51004") (pin "B5") (pinfunction "B5_B5") (pintype "passive"))
    )
    (net (code "168") (name "unconnected-(J51004-PadB6)") (class "Default")
      (node (ref "J51004") (pin "B6") (pinfunction "B6_B6") (pintype "passive"))
    )
    (net (code "169") (name "unconnected-(J51004-PadB7)") (class "Default")
      (node (ref "J51004") (pin "B7") (pinfunction "B7_B7") (pintype "passive"))
    )
    (net (code "170") (name "unconnected-(J51004-PadB8)") (class "Default")
      (node (ref "J51004") (pin "B8") (pinfunction "B8_B8") (pintype "passive"))
    )
    (net (code "171") (name "unconnected-(J51004-PadB9)") (class "Default")
      (node (ref "J51004") (pin "B9") (pinfunction "B9_B9") (pintype "passive"))
    )
    (net (code "172") (name "unconnected-(J51004-PadB10)") (class "Default")
      (node (ref "J51004") (pin "B10") (pinfunction "B10_B10") (pintype "passive"))
    )
    (net (code "173") (name "unconnected-(J51004-PadB11)") (class "Default")
      (node (ref "J51004") (pin "B11") (pinfunction "B11_B11") (pintype "passive"))
    )
    (net (code "174") (name "unconnected-(J51004-PadB12)") (class "Default")
      (node (ref "J51004") (pin "B12") (pinfunction "B12_B12") (pintype "passive"))
    )
    (net (code "175") (name "unconnected-(J51004-PadB13)") (class "Default")
      (node (ref "J51004") (pin "B13") (pinfunction "B13_B13") (pintype "passive"))
    )
    (net (code "176") (name "unconnected-(J51004-PadB14)") (class "Default")
      (node (ref "J51004") (pin "B14") (pinfunction "B14_B14") (pintype "passive"))
    )
    (net (code "177") (name "unconnected-(J51005-PadA2)") (class "Default")
      (node (ref "J51005") (pin "A2") (pinfunction "A2_A2") (pintype "passive"))
    )
    (net (code "178") (name "unconnected-(J51005-PadA3)") (class "Default")
      (node (ref "J51005") (pin "A3") (pinfunction "A3_A3") (pintype "passive"))
    )
    (net (code "179") (name "unconnected-(J51005-PadA4)") (class "Default")
      (node (ref "J51005") (pin "A4") (pinfunction "A4_A4") (pintype "passive"))
    )
    (net (code "180") (name "unconnected-(J51005-PadA5)") (class "Default")
      (node (ref "J51005") (pin "A5") (pinfunction "A5_A5") (pintype "passive"))
    )
    (net (code "181") (name "unconnected-(J51005-PadA6)") (class "Default")
      (node (ref "J51005") (pin "A6") (pinfunction "A6_A6") (pintype "passive"))
    )
    (net (code "182") (name "unconnected-(J51005-PadA7)") (class "Default")
      (node (ref "J51005") (pin "A7") (pinfunction "A7_A7") (pintype "passive"))
    )
    (net (code "183") (name "unconnected-(J51005-PadA8)") (class "Default")
      (node (ref "J51005") (pin "A8") (pinfunction "A8_A8") (pintype "passive"))
    )
    (net (code "184") (name "unconnected-(J51005-PadA9)") (class "Default")
      (node (ref "J51005") (pin "A9") (pinfunction "A9_A9") (pintype "passive"))
    )
    (net (code "185") (name "unconnected-(J51005-PadA10)") (class "Default")
      (node (ref "J51005") (pin "A10") (pinfunction "A10_A10") (pintype "passive"))
    )
    (net (code "186") (name "unconnected-(J51005-PadA11)") (class "Default")
      (node (ref "J51005") (pin "A11") (pinfunction "A11_A11") (pintype "passive"))
    )
    (net (code "187") (name "unconnected-(J51005-PadA12)") (class "Default")
      (node (ref "J51005") (pin "A12") (pinfunction "A12_A12") (pintype "passive"))
    )
    (net (code "188") (name "unconnected-(J51005-PadA13)") (class "Default")
      (node (ref "J51005") (pin "A13") (pinfunction "A13_A13") (pintype "passive"))
    )
    (net (code "189") (name "unconnected-(J51005-PadA14)") (class "Default")
      (node (ref "J51005") (pin "A14") (pinfunction "A14_A14") (pintype "passive"))
    )
    (net (code "190") (name "unconnected-(J51005-PadB1)") (class "Default")
      (node (ref "J51005") (pin "B1") (pinfunction "B1_B1") (pintype "passive"))
    )
    (net (code "191") (name "unconnected-(J51005-PadB2)") (class "Default")
      (node (ref "J51005") (pin "B2") (pinfunction "B2_B2") (pintype "passive"))
    )
    (net (code "192") (name "unconnected-(J51005-PadB3)") (class "Default")
      (node (ref "J51005") (pin "B3") (pinfunction "B3_B3") (pintype "passive"))
    )
    (net (code "193") (name "unconnected-(J51005-PadB4)") (class "Default")
      (node (ref "J51005") (pin "B4") (pinfunction "B4_B4") (pintype "passive"))
    )
    (net (code "194") (name "unconnected-(J51005-PadB5)") (class "Default")
      (node (ref "J51005") (pin "B5") (pinfunction "B5_B5") (pintype "passive"))
    )
    (net (code "195") (name "unconnected-(J51005-PadB6)") (class "Default")
      (node (ref "J51005") (pin "B6") (pinfunction "B6_B6") (pintype "passive"))
    )
    (net (code "196") (name "unconnected-(J51005-PadB7)") (class "Default")
      (node (ref "J51005") (pin "B7") (pinfunction "B7_B7") (pintype "passive"))
    )
    (net (code "197") (name "unconnected-(J51005-PadB8)") (class "Default")
      (node (ref "J51005") (pin "B8") (pinfunction "B8_B8") (pintype "passive"))
    )
    (net (code "198") (name "unconnected-(J51005-PadB9)") (class "Default")
      (node (ref "J51005") (pin "B9") (pinfunction "B9_B9") (pintype "passive"))
    )
    (net (code "199") (name "unconnected-(J51005-PadB10)") (class "Default")
      (node (ref "J51005") (pin "B10") (pinfunction "B10_B10") (pintype "passive"))
    )
    (net (code "200") (name "unconnected-(J51005-PadB11)") (class "Default")
      (node (ref "J51005") (pin "B11") (pinfunction "B11_B11") (pintype "passive"))
    )
    (net (code "201") (name "unconnected-(J51005-PadB12)") (class "Default")
      (node (ref "J51005") (pin "B12") (pinfunction "B12_B12") (pintype "passive"))
    )
    (net (code "202") (name "unconnected-(J51005-PadB13)") (class "Default")
      (node (ref "J51005") (pin "B13") (pinfunction "B13_B13") (pintype "passive"))
    )
    (net (code "203") (name "unconnected-(J51005-PadB14)") (class "Default")
      (node (ref "J51005") (pin "B14") (pinfunction "B14_B14") (pintype "passive"))
    )
    (net (code "204") (name "unconnected-(R51000-Pad2)") (class "Default")
      (node (ref "R51000") (pin "2") (pinfunction "2_2") (pintype "passive"))
    )
  )
)
